# Sensor.net
KiCad netlist of a schematic drawn in Altium Designer
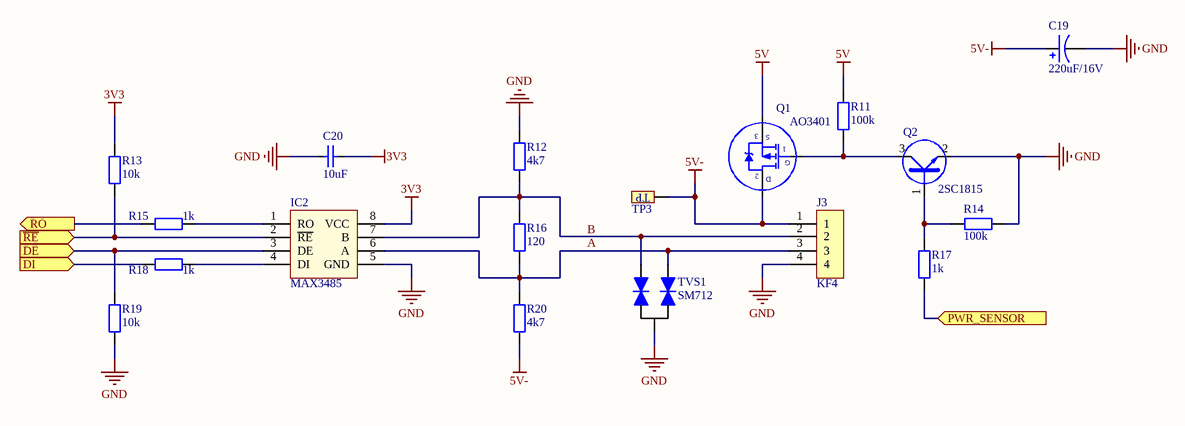
[diagram p0: Sensor.SchDoc]

(export (version "E")
  (design (tool "Eeschema 10.0.6"))
  (components
    (comp (ref "C19")
      (value "220uF/16V")
      (footprint "C5mm")
      (description "Polarized Capacitor (Axial)")
      (fields (field (name "PUBLISHER") "Altium Limited"))
      (libsource (lib "My Library") (part "Cap Pol"))
    )
    (comp (ref "C20")
      (value "10uF")
      (footprint "CAP_0805")
      (description "Capacitor")
      (fields (field (name "PUBLISHER") "Altium Limited"))
      (libsource (lib "My Library") (part "CapSMD"))
    )
    (comp (ref "IC2")
      (value "MAX3485")
      (footprint "SO-8")
      (description "RS232 - RS485 (Same sn75176)")
      (libsource (lib "My Library") (part "MAX485"))
    )
    (comp (ref "J3")
      (value "KF4")
      (footprint "KF4-5.08")
      (fields
        (field (name "MANUFACTURER") "Würth Elektronik eiSos GmbH")
        (field (name "PARTNO") "691133710004")
        (field (name "CREATED BY") "Baojun Chen")
      )
      (libsource (lib "My Library") (part "KF4"))
    )
    (comp (ref "Q1")
      (value "AO3401")
      (footprint "SOT23A")
      (description "30V 5.8A P-Channel MOSFET")
      (libsource (lib "My Library") (part "MOSFET_P"))
    )
    (comp (ref "Q2")
      (value "2SC1815")
      (footprint "SOT23D")
      (description "NPN 600mW, ECB")
      (libsource (lib "My Library") (part "C1815"))
    )
    (comp (ref "R11")
      (value "100k")
      (footprint "RES-SMD-0805")
      (description "Resistor SMD")
      (fields
        (field (name "MANUFACTURER") "Generic Components")
        (field (name "PUBLISHER") "Altium Hobart Technology Centre")
      )
      (libsource (lib "My Library") (part "Resistor - SMD"))
    )
    (comp (ref "R12")
      (value "4k7")
      (footprint "RES-SMD-0805")
      (description "Resistor SMD")
      (fields
        (field (name "MANUFACTURER") "Generic Components")
        (field (name "PUBLISHER") "Altium Hobart Technology Centre")
      )
      (libsource (lib "My Library") (part "Resistor - SMD"))
    )
    (comp (ref "R13")
      (value "10k")
      (footprint "RES-SMD-0805")
      (description "Resistor SMD")
      (fields
        (field (name "MANUFACTURER") "Generic Components")
        (field (name "PUBLISHER") "Altium Hobart Technology Centre")
      )
      (libsource (lib "My Library") (part "Resistor - SMD"))
    )
    (comp (ref "R14")
      (value "100k")
      (footprint "RES-SMD-0805")
      (description "Resistor SMD")
      (fields
        (field (name "MANUFACTURER") "Generic Components")
        (field (name "PUBLISHER") "Altium Hobart Technology Centre")
      )
      (libsource (lib "My Library") (part "Resistor - SMD"))
    )
    (comp (ref "R15")
      (value "1k")
      (footprint "RES-SMD-0805")
      (description "Resistor SMD")
      (fields
        (field (name "MANUFACTURER") "Generic Components")
        (field (name "PUBLISHER") "Altium Hobart Technology Centre")
      )
      (libsource (lib "My Library") (part "Resistor - SMD"))
    )
    (comp (ref "R16")
      (value "120")
      (footprint "RES-SMD-0805")
      (description "Resistor SMD")
      (fields
        (field (name "MANUFACTURER") "Generic Components")
        (field (name "PUBLISHER") "Altium Hobart Technology Centre")
      )
      (libsource (lib "My Library") (part "Resistor - SMD"))
    )
    (comp (ref "R17")
      (value "1k")
      (footprint "RES-SMD-0805")
      (description "Resistor SMD")
      (fields
        (field (name "MANUFACTURER") "Generic Components")
        (field (name "PUBLISHER") "Altium Hobart Technology Centre")
      )
      (libsource (lib "My Library") (part "Resistor - SMD"))
    )
    (comp (ref "R18")
      (value "1k")
      (footprint "RES-SMD-0805")
      (description "Resistor SMD")
      (fields
        (field (name "MANUFACTURER") "Generic Components")
        (field (name "PUBLISHER") "Altium Hobart Technology Centre")
      )
      (libsource (lib "My Library") (part "Resistor - SMD"))
    )
    (comp (ref "R19")
      (value "10k")
      (footprint "RES-SMD-0805")
      (description "Resistor SMD")
      (fields
        (field (name "MANUFACTURER") "Generic Components")
        (field (name "PUBLISHER") "Altium Hobart Technology Centre")
      )
      (libsource (lib "My Library") (part "Resistor - SMD"))
    )
    (comp (ref "R20")
      (value "4k7")
      (footprint "RES-SMD-0805")
      (description "Resistor SMD")
      (fields
        (field (name "MANUFACTURER") "Generic Components")
        (field (name "PUBLISHER") "Altium Hobart Technology Centre")
      )
      (libsource (lib "My Library") (part "Resistor - SMD"))
    )
    (comp (ref "TP3")
      (value "Test Point")
      (footprint "TP_SMD")
      (description "CONNECT 1")
      (libsource (lib "My Library") (part "TP"))
    )
    (comp (ref "TVS1")
      (value "SM712")
      (footprint "SOT23")
      (description "BAV70")
      (libsource (lib "My Library") (part "BAV70"))
    )
  )
  (nets
    (net (code "1") (name "/A") (class "Default")
      (node (ref "IC2") (pin "6") (pinfunction "A_6") (pintype "passive"))
      (node (ref "J3") (pin "3") (pinfunction "3_3") (pintype "passive"))
      (node (ref "R16") (pin "1") (pinfunction "1_1") (pintype "passive"))
      (node (ref "R20") (pin "2") (pinfunction "2_2") (pintype "passive"))
      (node (ref "TVS1") (pin "1") (pinfunction "A_1") (pintype "passive"))
    )
    (net (code "3") (name "/DE") (class "Default")
      (node (ref "IC2") (pin "3") (pinfunction "DE_3") (pintype "passive"))
      (node (ref "R19") (pin "1") (pinfunction "1_1") (pintype "passive"))
    )
    (net (code "4") (name "/DI") (class "Default")
      (node (ref "R18") (pin "2") (pinfunction "2_2") (pintype "passive"))
    )
    (net (code "5") (name "/PWR_SENSOR") (class "Default")
      (node (ref "R17") (pin "2") (pinfunction "2_2") (pintype "passive"))
    )
    (net (code "6") (name "/RO") (class "Default")
      (node (ref "R15") (pin "2") (pinfunction "2_2") (pintype "passive"))
    )
    (net (code "7") (name "/~{RE}") (class "Default")
      (node (ref "IC2") (pin "2") (pinfunction "~{RE}_2") (pintype "passive"))
      (node (ref "R13") (pin "2") (pinfunction "2_2") (pintype "passive"))
    )
    (net (code "8") (name "3V3") (class "Default")
      (node (ref "C20") (pin "2") (pinfunction "2_2") (pintype "passive"))
      (node (ref "IC2") (pin "8") (pinfunction "VCC_8") (pintype "passive"))
      (node (ref "R13") (pin "1") (pinfunction "1_1") (pintype "passive"))
    )
    (net (code "9") (name "5V") (class "Default")
      (node (ref "Q1") (pin "3") (pinfunction "S_3") (pintype "passive"))
      (node (ref "R11") (pin "1") (pinfunction "1_1") (pintype "passive"))
    )
    (net (code "10") (name "5V-") (class "Default")
      (node (ref "C19") (pin "1") (pinfunction "1_1") (pintype "passive"))
      (node (ref "J3") (pin "1") (pinfunction "1_1") (pintype "passive"))
      (node (ref "Q1") (pin "2") (pinfunction "D_2") (pintype "passive"))
      (node (ref "R20") (pin "1") (pinfunction "1_1") (pintype "passive"))
      (node (ref "TP3") (pin "1") (pinfunction "0_1") (pintype "passive"))
    )
    (net (code "11") (name "GND") (class "Default")
      (node (ref "C19") (pin "2") (pinfunction "2_2") (pintype "passive"))
      (node (ref "C20") (pin "1") (pinfunction "1_1") (pintype "passive"))
      (node (ref "IC2") (pin "5") (pinfunction "GND_5") (pintype "passive"))
      (node (ref "J3") (pin "4") (pinfunction "4_4") (pintype "passive"))
      (node (ref "Q2") (pin "2") (pinfunction "E_2") (pintype "passive"))
      (node (ref "R12") (pin "2") (pinfunction "2_2") (pintype "passive"))
      (node (ref "R14") (pin "2") (pinfunction "2_2") (pintype "passive"))
      (node (ref "R19") (pin "2") (pinfunction "2_2") (pintype "passive"))
      (node (ref "TVS1") (pin "3") (pinfunction "K_3") (pintype "passive"))
    )
    (net (code "12") (name "Net-(IC2-B)") (class "Default")
      (node (ref "IC2") (pin "7") (pinfunction "B_7") (pintype "passive"))
      (node (ref "J3") (pin "2") (pinfunction "2_2") (pintype "passive"))
      (node (ref "R12") (pin "1") (pinfunction "1_1") (pintype "passive"))
      (node (ref "R16") (pin "2") (pinfunction "2_2") (pintype "passive"))
      (node (ref "TVS1") (pin "2") (pinfunction "A_2") (pintype "passive"))
    )
    (net (code "13") (name "Net-(IC2-DI)") (class "Default")
      (node (ref "IC2") (pin "4") (pinfunction "DI_4") (pintype "passive"))
      (node (ref "R18") (pin "1") (pinfunction "1_1") (pintype "passive"))
    )
    (net (code "14") (name "Net-(IC2-RO)") (class "Default")
      (node (ref "IC2") (pin "1") (pinfunction "RO_1") (pintype "passive"))
      (node (ref "R15") (pin "1") (pinfunction "1_1") (pintype "passive"))
    )
    (net (code "15") (name "Net-(Q1-G)") (class "Default")
      (node (ref "Q1") (pin "1") (pinfunction "G_1") (pintype "passive"))
      (node (ref "Q2") (pin "3") (pinfunction "C_3") (pintype "passive"))
      (node (ref "R11") (pin "2") (pinfunction "2_2") (pintype "passive"))
    )
    (net (code "16") (name "Net-(Q2-B)") (class "Default")
      (node (ref "Q2") (pin "1") (pinfunction "B_1") (pintype "passive"))
      (node (ref "R14") (pin "1") (pinfunction "1_1") (pintype "passive"))
      (node (ref "R17") (pin "1") (pinfunction "1_1") (pintype "passive"))
    )
  )
)
